# VentMonSwitches.net
KiCad netlist of a schematic drawn in EAGLE
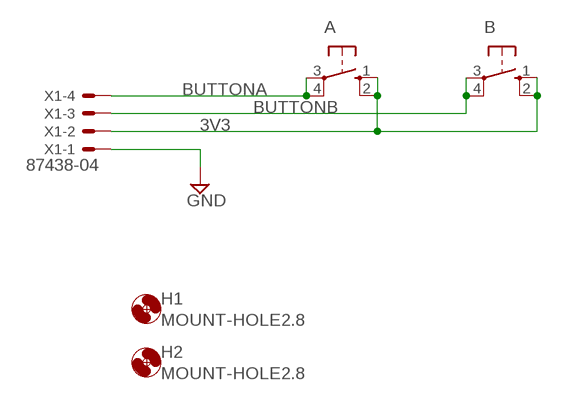
[diagram p0: schematic, sheet 1]

(export (version "E")
  (design (tool "Eeschema 10.0.6"))
  (components
    (comp (ref "A")
      (value "10-XX")
      (footprint "eagle-import:B3F-10XX")
      (fields (field (name "MPN") "B3F-1000"))
      (libsource (lib "eagle-import") (part "10-XX"))
    )
    (comp (ref "B")
      (value "10-XX")
      (footprint "eagle-import:B3F-10XX")
      (fields (field (name "MPN") "B3F-1000"))
      (libsource (lib "eagle-import") (part "10-XX"))
    )
    (comp (ref "H1")
      (value "MOUNT-HOLE2.8")
      (footprint "eagle-import:2,8")
      (libsource (lib "eagle-import") (part "MOUNT-HOLE2.8"))
    )
    (comp (ref "H2")
      (value "MOUNT-HOLE2.8")
      (footprint "eagle-import:2,8")
      (libsource (lib "eagle-import") (part "MOUNT-HOLE2.8"))
    )
    (comp (ref "X1")
      (value "87438-04")
      (footprint "eagle-import:87438-04")
      (fields (field (name "MF") "MOLEX"))
      (libsource (lib "eagle-import") (part "87438-04"))
    )
  )
  (nets
    (net (code "1") (name "/3V3") (class "Default")
      (node (ref "A") (pin "1") (pinfunction "S_1") (pintype "passive"))
      (node (ref "A") (pin "2") (pinfunction "S1_2") (pintype "passive"))
      (node (ref "B") (pin "1") (pinfunction "S_1") (pintype "passive"))
      (node (ref "B") (pin "2") (pinfunction "S1_2") (pintype "passive"))
      (node (ref "X1") (pin "2") (pinfunction "S_2") (pintype "passive"))
    )
    (net (code "2") (name "/BUTTONA") (class "Default")
      (node (ref "A") (pin "3") (pinfunction "P_3") (pintype "passive"))
      (node (ref "A") (pin "4") (pinfunction "P1_4") (pintype "passive"))
      (node (ref "X1") (pin "4") (pinfunction "S_4") (pintype "passive"))
    )
    (net (code "3") (name "/BUTTONB") (class "Default")
      (node (ref "B") (pin "3") (pinfunction "P_3") (pintype "passive"))
      (node (ref "B") (pin "4") (pinfunction "P1_4") (pintype "passive"))
      (node (ref "X1") (pin "3") (pinfunction "S_3") (pintype "passive"))
    )
    (net (code "4") (name "GND") (class "Default")
      (node (ref "X1") (pin "1") (pinfunction "S_1") (pintype "passive"))
    )
  )
)
